# Presencia_Agua.net
KiCad netlist of a schematic drawn in Altium Designer
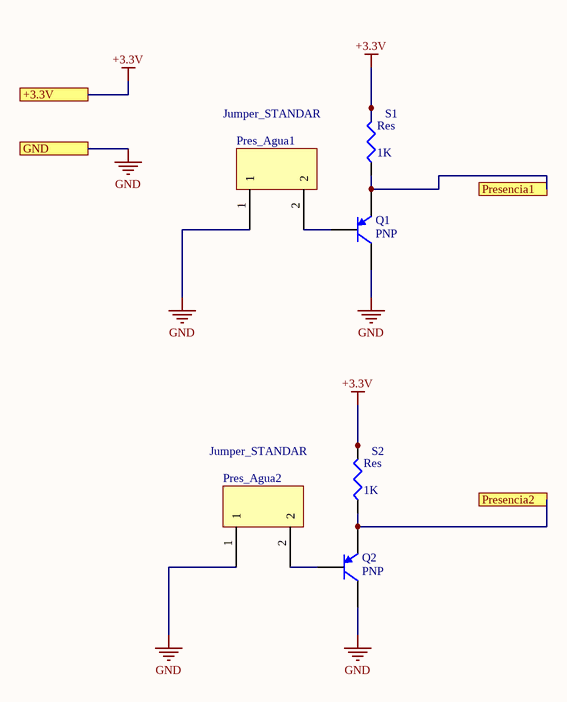
[diagram p0: Presencia_Agua.SchDoc]

(export (version "E")
  (design (tool "Eeschema 10.0.6"))
  (components
    (comp (ref "Pres_Agua1")
      (value "Jumper_STANDAR")
      (footprint "HDR1X2H")
      (libsource (lib "XSUB_COMP") (part "Jumper_STANDAR"))
    )
    (comp (ref "Pres_Agua2")
      (value "Jumper_STANDAR")
      (footprint "HDR1X2H")
      (libsource (lib "XSUB_COMP") (part "Jumper_STANDAR"))
    )
    (comp (ref "Q1")
      (value "PNP")
      (footprint "SOT-23B_L")
      (description "PNP Bipolar Transistor")
      (fields (field (name "PUBLISHER") "Altium Limited"))
      (libsource (lib "Miscellaneous Devices") (part "PNP"))
    )
    (comp (ref "Q2")
      (value "PNP")
      (footprint "SOT-23B_L")
      (description "PNP Bipolar Transistor")
      (fields (field (name "PUBLISHER") "Altium Limited"))
      (libsource (lib "Miscellaneous Devices") (part "PNP"))
    )
    (comp (ref "S1")
      (value "Res")
      (footprint "6-0805_L")
      (description "Resistor")
      (fields (field (name "ALTIUM_VALUE") "1K") (field (name "PUBLISHER") "Altium Limited"))
      (libsource (lib "Miscellaneous Devices") (part "Res3"))
    )
    (comp (ref "S2")
      (value "Res")
      (footprint "6-0805_L")
      (description "Resistor")
      (fields (field (name "ALTIUM_VALUE") "1K") (field (name "PUBLISHER") "Altium Limited"))
      (libsource (lib "Miscellaneous Devices") (part "Res3"))
    )
  )
  (nets
    (net (code "1") (name "+3.3V") (class "Default")
      (node (ref "S1") (pin "2") (pinfunction "2_2") (pintype "passive"))
      (node (ref "S2") (pin "2") (pinfunction "2_2") (pintype "passive"))
    )
    (net (code "2") (name "/Presencia1") (class "Default")
      (node (ref "Q1") (pin "3") (pinfunction "E_3") (pintype "passive"))
      (node (ref "S1") (pin "1") (pinfunction "1_1") (pintype "passive"))
    )
    (net (code "3") (name "/Presencia2") (class "Default")
      (node (ref "Q2") (pin "3") (pinfunction "E_3") (pintype "passive"))
      (node (ref "S2") (pin "1") (pinfunction "1_1") (pintype "passive"))
    )
    (net (code "4") (name "GND") (class "Default")
      (node (ref "Pres_Agua1") (pin "1") (pinfunction "1_1") (pintype "passive"))
      (node (ref "Pres_Agua2") (pin "1") (pinfunction "1_1") (pintype "passive"))
      (node (ref "Q1") (pin "1") (pinfunction "C_1") (pintype "passive"))
      (node (ref "Q2") (pin "1") (pinfunction "C_1") (pintype "passive"))
    )
    (net (code "5") (name "Net-(Q1-B)") (class "Default")
      (node (ref "Pres_Agua1") (pin "2") (pinfunction "2_2") (pintype "passive"))
      (node (ref "Q1") (pin "2") (pinfunction "B_2") (pintype "passive"))
    )
    (net (code "6") (name "Net-(Q2-B)") (class "Default")
      (node (ref "Pres_Agua2") (pin "2") (pinfunction "2_2") (pintype "passive"))
      (node (ref "Q2") (pin "2") (pinfunction "B_2") (pintype "passive"))
    )
  )
)
